# 2020.net
KiCad netlist of a schematic drawn in Altium Designer
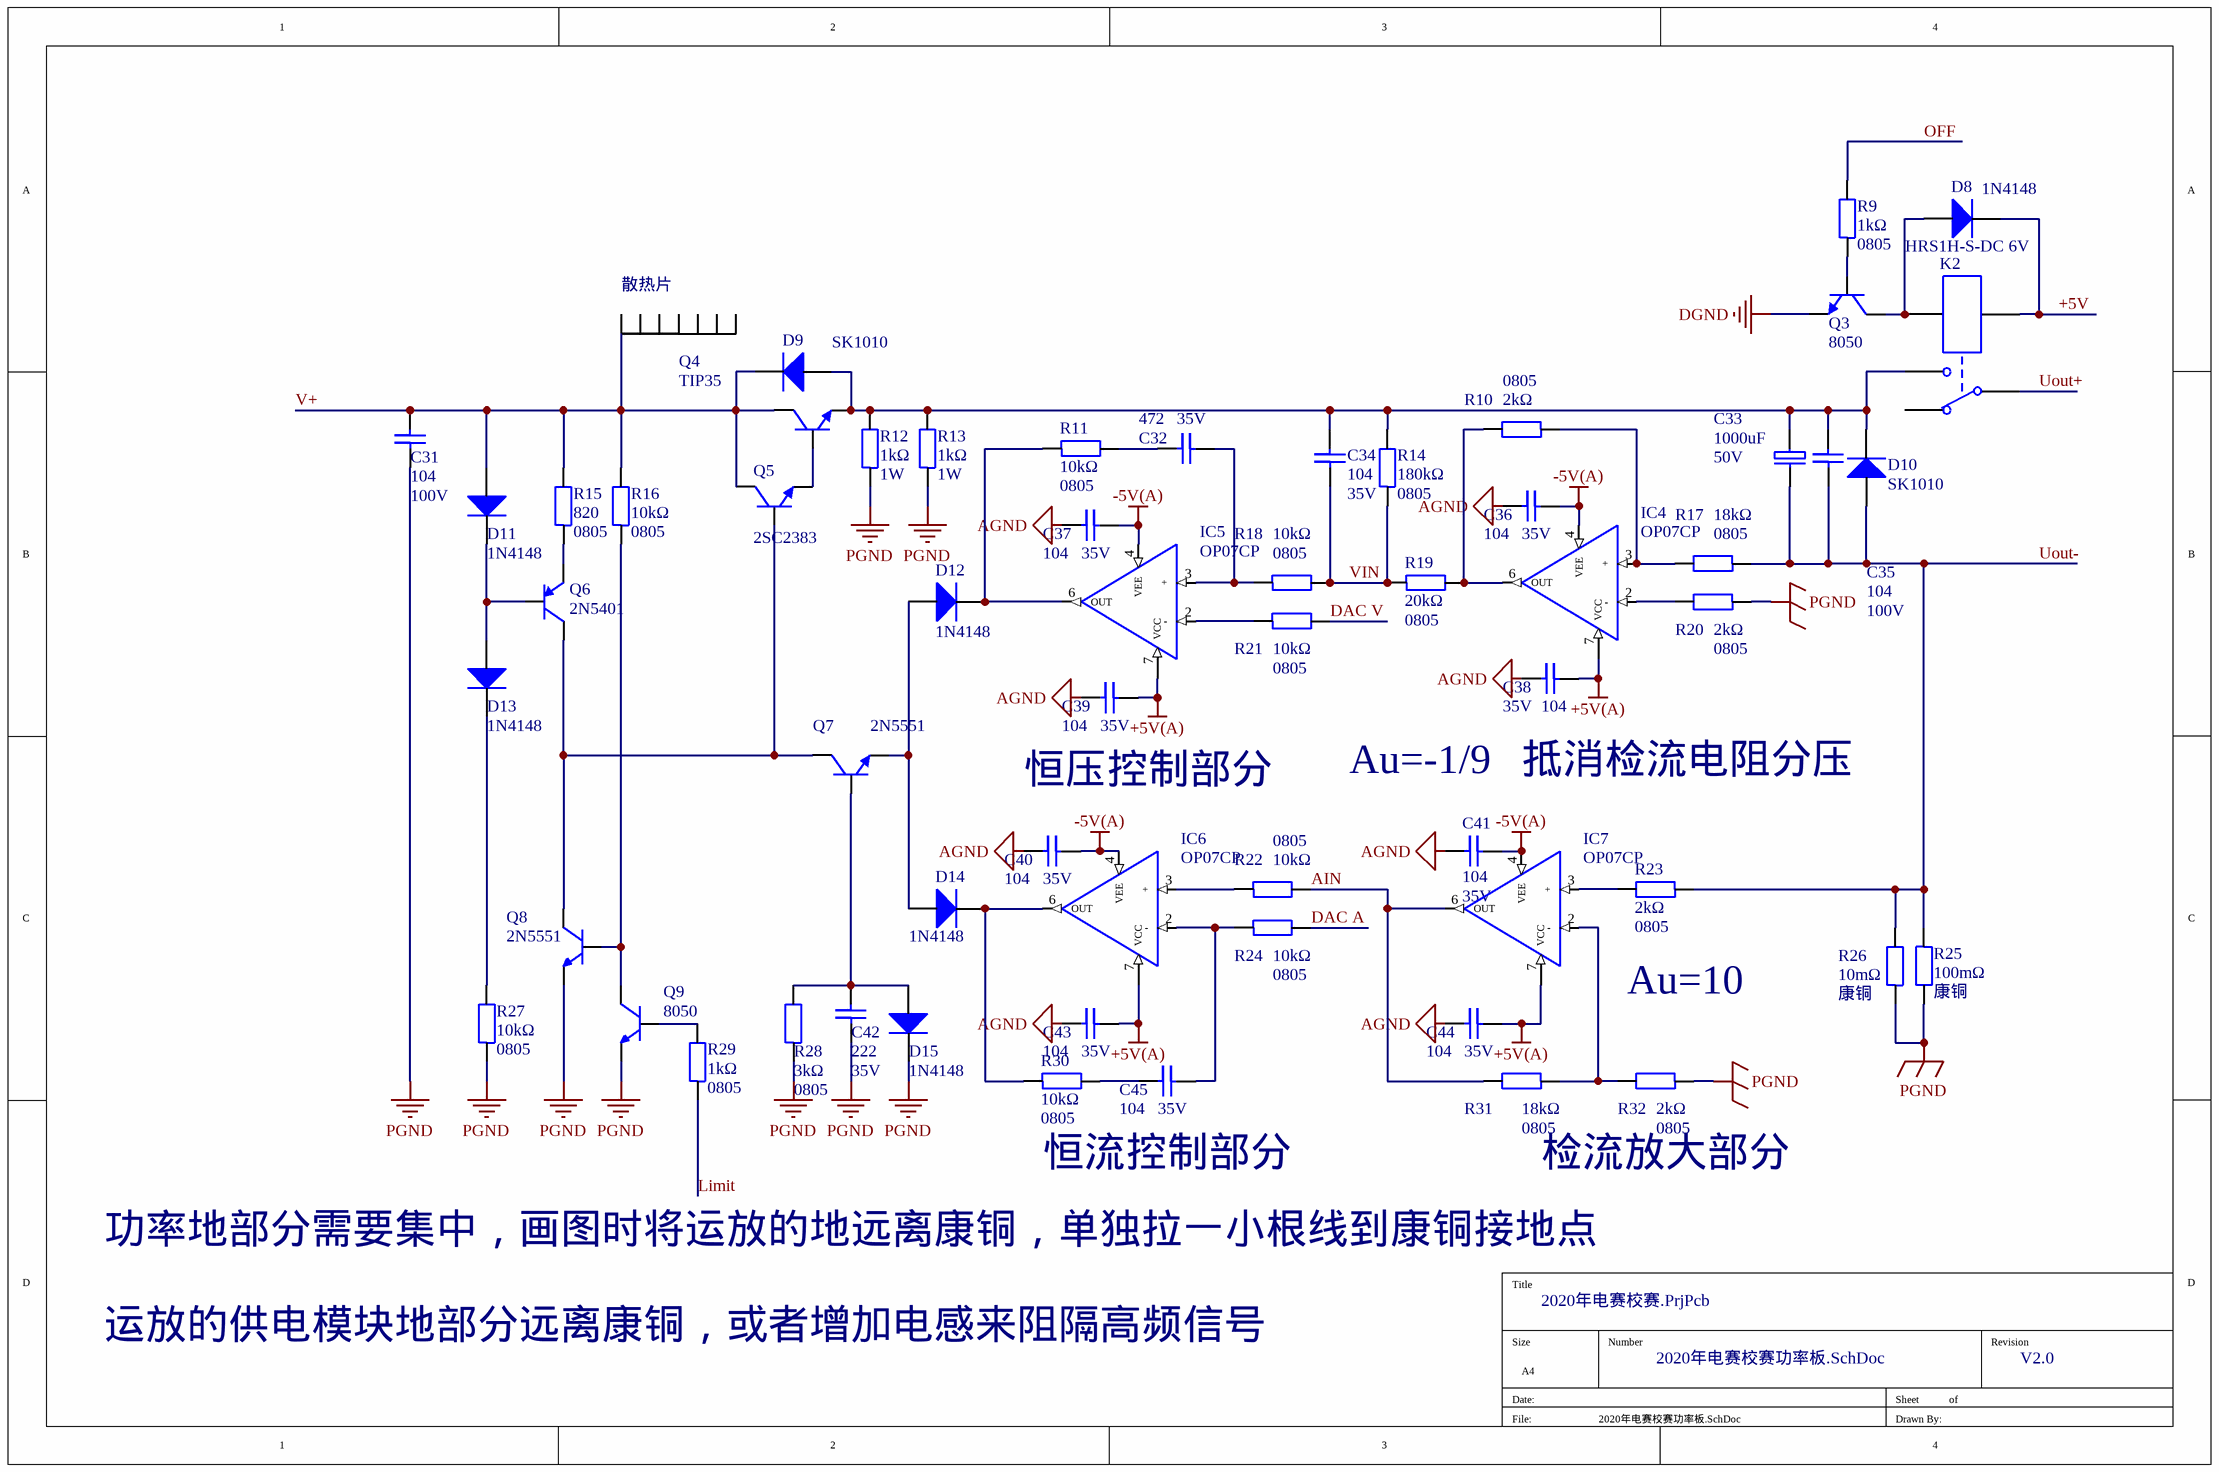
[diagram p0: 2020年电赛校赛功率板.SchDoc]

(export (version "E")
  (design (tool "Eeschema 10.0.6"))
  (components
    (comp (ref "C31")
      (value "104")
      (footprint "C0805")
      (description "无极性电容")
      (fields (field (name "ALTIUM_VALUE") "100V"))
      (libsource (lib "原理图库") (part "104"))
    )
    (comp (ref "C32")
      (value "472")
      (footprint "C0805")
      (description "无极性电容")
      (fields (field (name "ALTIUM_VALUE") "35V"))
      (libsource (lib "原理图库") (part "104"))
    )
    (comp (ref "C33")
      (value "1000uF")
      (footprint "50V 1000uF")
      (description "有极性电容")
      (fields (field (name "ALTIUM_VALUE") "50V"))
      (libsource (lib "原理图库") (part "100uF"))
    )
    (comp (ref "C34")
      (value "104")
      (footprint "C0805")
      (description "无极性电容")
      (fields (field (name "ALTIUM_VALUE") "35V"))
      (libsource (lib "原理图库") (part "104"))
    )
    (comp (ref "C35")
      (value "104")
      (footprint "C0805")
      (description "无极性电容")
      (fields (field (name "ALTIUM_VALUE") "100V"))
      (libsource (lib "原理图库") (part "104"))
    )
    (comp (ref "C36")
      (value "104")
      (footprint "C0805")
      (description "无极性电容")
      (fields (field (name "ALTIUM_VALUE") "35V"))
      (libsource (lib "原理图库") (part "104"))
    )
    (comp (ref "C37")
      (value "104")
      (footprint "C0805")
      (description "无极性电容")
      (fields (field (name "ALTIUM_VALUE") "35V"))
      (libsource (lib "原理图库") (part "104"))
    )
    (comp (ref "C38")
      (value "104")
      (footprint "C0805")
      (description "无极性电容")
      (fields (field (name "ALTIUM_VALUE") "35V"))
      (libsource (lib "原理图库") (part "104"))
    )
    (comp (ref "C39")
      (value "104")
      (footprint "C0805")
      (description "无极性电容")
      (fields (field (name "ALTIUM_VALUE") "35V"))
      (libsource (lib "原理图库") (part "104"))
    )
    (comp (ref "C40")
      (value "104")
      (footprint "C0805")
      (description "无极性电容")
      (fields (field (name "ALTIUM_VALUE") "35V"))
      (libsource (lib "原理图库") (part "104"))
    )
    (comp (ref "C41")
      (value "104")
      (footprint "C0805")
      (description "无极性电容")
      (fields (field (name "ALTIUM_VALUE") "35V"))
      (libsource (lib "原理图库") (part "104"))
    )
    (comp (ref "C42")
      (value "222")
      (footprint "C0805")
      (description "无极性电容")
      (fields (field (name "ALTIUM_VALUE") "35V"))
      (libsource (lib "原理图库") (part "104"))
    )
    (comp (ref "C43")
      (value "104")
      (footprint "C0805")
      (description "无极性电容")
      (fields (field (name "ALTIUM_VALUE") "35V"))
      (libsource (lib "原理图库") (part "104"))
    )
    (comp (ref "C44")
      (value "104")
      (footprint "C0805")
      (description "无极性电容")
      (fields (field (name "ALTIUM_VALUE") "35V"))
      (libsource (lib "原理图库") (part "104"))
    )
    (comp (ref "C45")
      (value "104")
      (footprint "C0805")
      (description "无极性电容")
      (fields (field (name "ALTIUM_VALUE") "35V"))
      (libsource (lib "原理图库") (part "104"))
    )
    (comp (ref "D8")
      (value "1N4148")
      (footprint "LL34")
      (description "二极管")
      (libsource (lib "原理图库") (part "Diode"))
    )
    (comp (ref "D9")
      (value "SK1010")
      (footprint "SMC(DO-214AB)")
      (description "二极管")
      (libsource (lib "原理图库") (part "Diode"))
    )
    (comp (ref "D10")
      (value "SK1010")
      (footprint "SMC(DO-214AB)")
      (description "二极管")
      (libsource (lib "原理图库") (part "Diode"))
    )
    (comp (ref "D11")
      (value "1N4148")
      (footprint "LL34")
      (description "二极管")
      (libsource (lib "原理图库") (part "Diode"))
    )
    (comp (ref "D12")
      (value "1N4148")
      (footprint "LL34")
      (description "二极管")
      (libsource (lib "原理图库") (part "Diode"))
    )
    (comp (ref "D13")
      (value "1N4148")
      (footprint "LL34")
      (description "二极管")
      (libsource (lib "原理图库") (part "Diode"))
    )
    (comp (ref "D14")
      (value "1N4148")
      (footprint "LL34")
      (description "二极管")
      (libsource (lib "原理图库") (part "Diode"))
    )
    (comp (ref "D15")
      (value "1N4148")
      (footprint "LL34")
      (description "二极管")
      (libsource (lib "原理图库") (part "Diode"))
    )
    (comp (ref "IC4")
      (value "OP07CP")
      (footprint "SOP-8(体宽3.8mm)")
      (description "运放")
      (libsource (lib "原理图库") (part "OP07CP"))
    )
    (comp (ref "IC5")
      (value "OP07CP")
      (footprint "SOP-8(体宽3.8mm)")
      (description "运放")
      (libsource (lib "原理图库") (part "OP07CP"))
    )
    (comp (ref "IC6")
      (value "OP07CP")
      (footprint "SOP-8(体宽3.8mm)")
      (description "运放")
      (libsource (lib "原理图库") (part "OP07CP"))
    )
    (comp (ref "IC7")
      (value "OP07CP")
      (footprint "SOP-8(体宽3.8mm)")
      (description "运放")
      (libsource (lib "原理图库") (part "OP07CP"))
    )
    (comp (ref "K2")
      (value "HRS1H-S-DC 6V")
      (footprint "HRS1H-S-DC 6V")
      (description "继电器")
      (libsource (lib "原理图库") (part "HRS1H-S-DC 6V"))
    )
    (comp (ref "Q3")
      (value "8050")
      (footprint "SOT-23")
      (description "三极管")
      (libsource (lib "") (part "NPN_2"))
    )
    (comp (ref "Q4")
      (value "TIP35")
      (footprint "TO-247")
      (description "三极管")
      (libsource (lib "原理图库") (part "NPN"))
    )
    (comp (ref "Q5")
      (value "2SC2383")
      (footprint "TO-92")
      (description "三极管")
      (libsource (lib "") (part "NPN_1"))
    )
    (comp (ref "Q6") (value "2N5401") (footprint "SOT-23") (libsource (lib "原理图库") (part "PNP")))
    (comp (ref "Q7")
      (value "2N5551")
      (footprint "SOT-23")
      (description "三极管")
      (libsource (lib "") (part "NPN_2"))
    )
    (comp (ref "Q8") (value "2N5551") (footprint "SOT-23") (libsource (lib "原理图库") (part "NPN!")))
    (comp (ref "Q9")
      (value "8050")
      (footprint "SOT-23")
      (description "三极管")
      (libsource (lib "原理图库") (part "NPN!"))
    )
    (comp (ref "R9")
      (value "1kΩ")
      (footprint "R0805")
      (description "贴片/直插电阻")
      (fields (field (name "ALTIUM_VALUE") "0805"))
      (libsource (lib "原理图库") (part "10kΩ"))
    )
    (comp (ref "R10")
      (value "2kΩ")
      (footprint "R0805")
      (description "贴片/直插电阻")
      (fields (field (name "ALTIUM_VALUE") "0805"))
      (libsource (lib "原理图库") (part "10kΩ"))
    )
    (comp (ref "R11")
      (value "10kΩ")
      (footprint "R0805")
      (description "贴片/直插电阻")
      (fields (field (name "ALTIUM_VALUE") "0805"))
      (libsource (lib "原理图库") (part "10kΩ"))
    )
    (comp (ref "R12")
      (value "1kΩ")
      (footprint "Res-1W")
      (description "贴片/直插电阻")
      (fields (field (name "ALTIUM_VALUE") "1W"))
      (libsource (lib "原理图库") (part "10kΩ"))
    )
    (comp (ref "R13")
      (value "1kΩ")
      (footprint "Res-1W")
      (description "贴片/直插电阻")
      (fields (field (name "ALTIUM_VALUE") "1W"))
      (libsource (lib "原理图库") (part "10kΩ"))
    )
    (comp (ref "R14")
      (value "180kΩ")
      (footprint "R0805")
      (description "贴片/直插电阻")
      (fields (field (name "ALTIUM_VALUE") "0805"))
      (libsource (lib "原理图库") (part "10kΩ"))
    )
    (comp (ref "R15")
      (value "820")
      (footprint "R0805")
      (description "贴片/直插电阻")
      (fields (field (name "ALTIUM_VALUE") "0805"))
      (libsource (lib "原理图库") (part "10kΩ"))
    )
    (comp (ref "R16")
      (value "10kΩ")
      (footprint "R0805")
      (description "贴片/直插电阻")
      (fields (field (name "ALTIUM_VALUE") "0805"))
      (libsource (lib "原理图库") (part "10kΩ"))
    )
    (comp (ref "R17")
      (value "18kΩ")
      (footprint "R0805")
      (description "贴片/直插电阻")
      (fields (field (name "ALTIUM_VALUE") "0805"))
      (libsource (lib "原理图库") (part "10kΩ"))
    )
    (comp (ref "R18")
      (value "10kΩ")
      (footprint "R0805")
      (description "贴片/直插电阻")
      (fields (field (name "ALTIUM_VALUE") "0805"))
      (libsource (lib "原理图库") (part "10kΩ"))
    )
    (comp (ref "R19")
      (value "20kΩ")
      (footprint "R0805")
      (description "贴片/直插电阻")
      (fields (field (name "ALTIUM_VALUE") "0805"))
      (libsource (lib "原理图库") (part "10kΩ"))
    )
    (comp (ref "R20")
      (value "2kΩ")
      (footprint "R0805")
      (description "贴片/直插电阻")
      (fields (field (name "ALTIUM_VALUE") "0805"))
      (libsource (lib "原理图库") (part "10kΩ"))
    )
    (comp (ref "R21")
      (value "10kΩ")
      (footprint "R0805")
      (description "贴片/直插电阻")
      (fields (field (name "ALTIUM_VALUE") "0805"))
      (libsource (lib "原理图库") (part "10kΩ"))
    )
    (comp (ref "R22")
      (value "10kΩ")
      (footprint "R0805")
      (description "贴片/直插电阻")
      (fields (field (name "ALTIUM_VALUE") "0805"))
      (libsource (lib "原理图库") (part "10kΩ"))
    )
    (comp (ref "R23")
      (value "2kΩ")
      (footprint "R0805")
      (description "贴片/直插电阻")
      (fields (field (name "ALTIUM_VALUE") "0805"))
      (libsource (lib "原理图库") (part "10kΩ"))
    )
    (comp (ref "R24")
      (value "10kΩ")
      (footprint "R0805")
      (description "贴片/直插电阻")
      (fields (field (name "ALTIUM_VALUE") "0805"))
      (libsource (lib "原理图库") (part "10kΩ"))
    )
    (comp (ref "R25")
      (value "100mΩ")
      (footprint "100mΩ康铜")
      (description "贴片/直插电阻")
      (fields (field (name "ALTIUM_VALUE") "康铜"))
      (libsource (lib "原理图库") (part "10kΩ"))
    )
    (comp (ref "R26")
      (value "10mΩ")
      (footprint "10mΩ康铜")
      (description "贴片/直插电阻")
      (fields (field (name "ALTIUM_VALUE") "康铜"))
      (libsource (lib "原理图库") (part "10kΩ"))
    )
    (comp (ref "R27")
      (value "10kΩ")
      (footprint "R0805")
      (description "贴片/直插电阻")
      (fields (field (name "ALTIUM_VALUE") "0805"))
      (libsource (lib "原理图库") (part "10kΩ"))
    )
    (comp (ref "R28")
      (value "3kΩ")
      (footprint "R0805")
      (description "贴片/直插电阻")
      (fields (field (name "ALTIUM_VALUE") "0805"))
      (libsource (lib "原理图库") (part "10kΩ"))
    )
    (comp (ref "R29")
      (value "1kΩ")
      (footprint "R0805")
      (description "贴片/直插电阻")
      (fields (field (name "ALTIUM_VALUE") "0805"))
      (libsource (lib "原理图库") (part "10kΩ"))
    )
    (comp (ref "R30")
      (value "10kΩ")
      (footprint "R0805")
      (description "贴片/直插电阻")
      (fields (field (name "ALTIUM_VALUE") "0805"))
      (libsource (lib "原理图库") (part "10kΩ"))
    )
    (comp (ref "R31")
      (value "18kΩ")
      (footprint "R0805")
      (description "贴片/直插电阻")
      (fields (field (name "ALTIUM_VALUE") "0805"))
      (libsource (lib "原理图库") (part "10kΩ"))
    )
    (comp (ref "R32")
      (value "2kΩ")
      (footprint "R0805")
      (description "贴片/直插电阻")
      (fields (field (name "ALTIUM_VALUE") "0805"))
      (libsource (lib "原理图库") (part "10kΩ"))
    )
    (comp (ref "S1") (value "散热片") (footprint "散热片") (libsource (lib "原理图库") (part "散热片")))
  )
  (nets
    (net (code "1") (name "+5V(A)") (class "Default")
      (node (ref "C38") (pin "2") (pintype "passive"))
      (node (ref "C39") (pin "2") (pintype "passive"))
      (node (ref "C43") (pin "2") (pintype "passive"))
      (node (ref "C44") (pin "2") (pintype "passive"))
      (node (ref "IC4") (pin "7") (pinfunction "VCC_7") (pintype "input"))
      (node (ref "IC5") (pin "7") (pinfunction "VCC_7") (pintype "input"))
      (node (ref "IC6") (pin "7") (pinfunction "VCC_7") (pintype "input"))
      (node (ref "IC7") (pin "7") (pinfunction "VCC_7") (pintype "input"))
    )
    (net (code "2") (name "-5V(A)") (class "Default")
      (node (ref "C36") (pin "2") (pintype "passive"))
      (node (ref "C37") (pin "2") (pintype "passive"))
      (node (ref "C40") (pin "2") (pintype "passive"))
      (node (ref "C41") (pin "2") (pintype "passive"))
      (node (ref "IC4") (pin "4") (pinfunction "VEE_4") (pintype "input"))
      (node (ref "IC5") (pin "4") (pinfunction "VEE_4") (pintype "input"))
      (node (ref "IC6") (pin "4") (pinfunction "VEE_4") (pintype "input"))
      (node (ref "IC7") (pin "4") (pinfunction "VEE_4") (pintype "input"))
    )
    (net (code "3") (name "/+5V") (class "Default")
      (node (ref "D8") (pin "2") (pinfunction "K_2") (pintype "passive"))
      (node (ref "K2") (pin "2") (pinfunction "2_2") (pintype "passive"))
    )
    (net (code "4") (name "/AIN") (class "Default")
      (node (ref "IC7") (pin "6") (pinfunction "OUT_6") (pintype "output"))
      (node (ref "R22") (pin "2") (pintype "passive"))
      (node (ref "R31") (pin "2") (pintype "passive"))
    )
    (net (code "5") (name "/DAC A") (class "Default") (node (ref "R24") (pin "2") (pintype "passive")))
    (net (code "6") (name "/DAC V") (class "Default") (node (ref "R21") (pin "2") (pintype "passive")))
    (net (code "7") (name "/Limit") (class "Default") (node (ref "R29") (pin "1") (pintype "passive")))
    (net (code "8") (name "/OFF") (class "Default") (node (ref "R9") (pin "2") (pintype "passive")))
    (net (code "9") (name "/Uout+") (class "Default")
      (node (ref "K2") (pin "4") (pinfunction "4_4") (pintype "passive"))
    )
    (net (code "10") (name "/Uout-") (class "Default")
      (node (ref "C33") (pin "2") (pinfunction "-_2") (pintype "passive"))
      (node (ref "C35") (pin "1") (pintype "passive"))
      (node (ref "D10") (pin "1") (pinfunction "A_1") (pintype "passive"))
      (node (ref "R17") (pin "1") (pintype "passive"))
      (node (ref "R23") (pin "1") (pintype "passive"))
      (node (ref "R25") (pin "1") (pintype "passive"))
      (node (ref "R26") (pin "2") (pintype "passive"))
    )
    (net (code "11") (name "/V+") (class "Default")
      (node (ref "C31") (pin "2") (pintype "passive"))
      (node (ref "D11") (pin "1") (pinfunction "A_1") (pintype "passive"))
      (node (ref "D9") (pin "2") (pinfunction "K_2") (pintype "passive"))
      (node (ref "Q4") (pin "2") (pinfunction "C_2") (pintype "passive"))
      (node (ref "Q5") (pin "2") (pinfunction "C_2") (pintype "passive"))
      (node (ref "R15") (pin "2") (pintype "passive"))
      (node (ref "R16") (pin "2") (pintype "passive"))
      (node (ref "S1") (pin "1") (pintype "passive"))
    )
    (net (code "12") (name "/VIN") (class "Default")
      (node (ref "C34") (pin "1") (pintype "passive"))
      (node (ref "R14") (pin "1") (pintype "passive"))
      (node (ref "R18") (pin "2") (pintype "passive"))
      (node (ref "R19") (pin "1") (pintype "passive"))
    )
    (net (code "13") (name "AGND") (class "Default")
      (node (ref "C36") (pin "1") (pintype "passive"))
      (node (ref "C37") (pin "1") (pintype "passive"))
      (node (ref "C38") (pin "1") (pintype "passive"))
      (node (ref "C39") (pin "1") (pintype "passive"))
      (node (ref "C40") (pin "1") (pintype "passive"))
      (node (ref "C41") (pin "1") (pintype "passive"))
      (node (ref "C43") (pin "1") (pintype "passive"))
      (node (ref "C44") (pin "1") (pintype "passive"))
    )
    (net (code "14") (name "DGND") (class "Default")
      (node (ref "Q3") (pin "2") (pinfunction "E_2") (pintype "passive"))
    )
    (net (code "15") (name "Net-(C32-Pad1)") (class "Default")
      (node (ref "C32") (pin "1") (pintype "passive"))
      (node (ref "R11") (pin "2") (pintype "passive"))
    )
    (net (code "16") (name "Net-(C33-+)") (class "Default")
      (node (ref "C33") (pin "1") (pinfunction "+_1") (pintype "passive"))
      (node (ref "C34") (pin "2") (pintype "passive"))
      (node (ref "C35") (pin "2") (pintype "passive"))
      (node (ref "D10") (pin "2") (pinfunction "K_2") (pintype "passive"))
      (node (ref "D9") (pin "1") (pinfunction "A_1") (pintype "passive"))
      (node (ref "K2") (pin "6") (pinfunction "6_6") (pintype "passive"))
      (node (ref "Q4") (pin "3") (pinfunction "E_3") (pintype "passive"))
      (node (ref "R12") (pin "2") (pintype "passive"))
      (node (ref "R13") (pin "2") (pintype "passive"))
      (node (ref "R14") (pin "2") (pintype "passive"))
    )
    (net (code "17") (name "Net-(C45-Pad1)") (class "Default")
      (node (ref "C45") (pin "1") (pintype "passive"))
      (node (ref "R30") (pin "2") (pintype "passive"))
    )
    (net (code "18") (name "Net-(D8-A)") (class "Default")
      (node (ref "D8") (pin "1") (pinfunction "A_1") (pintype "passive"))
      (node (ref "K2") (pin "5") (pinfunction "5_5") (pintype "passive"))
      (node (ref "Q3") (pin "3") (pinfunction "C_3") (pintype "passive"))
    )
    (net (code "19") (name "Net-(D11-K)") (class "Default")
      (node (ref "D11") (pin "2") (pinfunction "K_2") (pintype "passive"))
      (node (ref "D13") (pin "1") (pinfunction "A_1") (pintype "passive"))
      (node (ref "Q6") (pin "1") (pinfunction "B_1") (pintype "passive"))
    )
    (net (code "20") (name "Net-(D12-A)") (class "Default")
      (node (ref "D12") (pin "1") (pinfunction "A_1") (pintype "passive"))
      (node (ref "D14") (pin "1") (pinfunction "A_1") (pintype "passive"))
      (node (ref "Q7") (pin "2") (pinfunction "E_2") (pintype "passive"))
    )
    (net (code "21") (name "Net-(D12-K)") (class "Default")
      (node (ref "D12") (pin "2") (pinfunction "K_2") (pintype "passive"))
      (node (ref "IC5") (pin "6") (pinfunction "OUT_6") (pintype "output"))
      (node (ref "R11") (pin "1") (pintype "passive"))
    )
    (net (code "22") (name "Net-(D13-K)") (class "Default")
      (node (ref "D13") (pin "2") (pinfunction "K_2") (pintype "passive"))
      (node (ref "R27") (pin "2") (pintype "passive"))
    )
    (net (code "23") (name "Net-(D14-K)") (class "Default")
      (node (ref "D14") (pin "2") (pinfunction "K_2") (pintype "passive"))
      (node (ref "IC6") (pin "6") (pinfunction "OUT_6") (pintype "output"))
      (node (ref "R30") (pin "1") (pintype "passive"))
    )
    (net (code "24") (name "Net-(D15-A)") (class "Default")
      (node (ref "C42") (pin "2") (pintype "passive"))
      (node (ref "D15") (pin "1") (pinfunction "A_1") (pintype "passive"))
      (node (ref "Q7") (pin "1") (pinfunction "B_1") (pintype "passive"))
      (node (ref "R28") (pin "2") (pintype "passive"))
    )
    (net (code "25") (name "Net-(IC4-+)") (class "Default")
      (node (ref "IC4") (pin "3") (pinfunction "+_3") (pintype "input"))
      (node (ref "R10") (pin "1") (pintype "passive"))
      (node (ref "R17") (pin "2") (pintype "passive"))
    )
    (net (code "26") (name "Net-(IC4--)") (class "Default")
      (node (ref "IC4") (pin "2") (pinfunction "-_2") (pintype "input"))
      (node (ref "R20") (pin "2") (pintype "passive"))
    )
    (net (code "27") (name "Net-(IC4-OUT)") (class "Default")
      (node (ref "IC4") (pin "6") (pinfunction "OUT_6") (pintype "output"))
      (node (ref "R10") (pin "2") (pintype "passive"))
      (node (ref "R19") (pin "2") (pintype "passive"))
    )
    (net (code "28") (name "Net-(IC5-+)") (class "Default")
      (node (ref "C32") (pin "2") (pintype "passive"))
      (node (ref "IC5") (pin "3") (pinfunction "+_3") (pintype "input"))
      (node (ref "R18") (pin "1") (pintype "passive"))
    )
    (net (code "29") (name "Net-(IC5--)") (class "Default")
      (node (ref "IC5") (pin "2") (pinfunction "-_2") (pintype "input"))
      (node (ref "R21") (pin "1") (pintype "passive"))
    )
    (net (code "30") (name "Net-(IC6-+)") (class "Default")
      (node (ref "IC6") (pin "3") (pinfunction "+_3") (pintype "input"))
      (node (ref "R22") (pin "1") (pintype "passive"))
    )
    (net (code "31") (name "Net-(IC6--)") (class "Default")
      (node (ref "C45") (pin "2") (pintype "passive"))
      (node (ref "IC6") (pin "2") (pinfunction "-_2") (pintype "input"))
      (node (ref "R24") (pin "1") (pintype "passive"))
    )
    (net (code "32") (name "Net-(IC7-+)") (class "Default")
      (node (ref "IC7") (pin "3") (pinfunction "+_3") (pintype "input"))
      (node (ref "R23") (pin "2") (pintype "passive"))
    )
    (net (code "33") (name "Net-(IC7--)") (class "Default")
      (node (ref "IC7") (pin "2") (pinfunction "-_2") (pintype "input"))
      (node (ref "R31") (pin "1") (pintype "passive"))
      (node (ref "R32") (pin "2") (pintype "passive"))
    )
    (net (code "34") (name "Net-(Q3-B)") (class "Default")
      (node (ref "Q3") (pin "1") (pinfunction "B_1") (pintype "passive"))
      (node (ref "R9") (pin "1") (pintype "passive"))
    )
    (net (code "35") (name "Net-(Q4-B)") (class "Default")
      (node (ref "Q4") (pin "1") (pinfunction "B_1") (pintype "passive"))
      (node (ref "Q5") (pin "1") (pinfunction "E_1") (pintype "passive"))
    )
    (net (code "36") (name "Net-(Q5-B)") (class "Default")
      (node (ref "Q5") (pin "3") (pinfunction "B_3") (pintype "passive"))
      (node (ref "Q6") (pin "3") (pinfunction "C_3") (pintype "passive"))
      (node (ref "Q7") (pin "3") (pinfunction "C_3") (pintype "passive"))
      (node (ref "Q8") (pin "3") (pinfunction "C_3") (pintype "passive"))
    )
    (net (code "37") (name "Net-(Q6-E)") (class "Default")
      (node (ref "Q6") (pin "2") (pinfunction "E_2") (pintype "passive"))
      (node (ref "R15") (pin "1") (pintype "passive"))
    )
    (net (code "38") (name "Net-(Q8-B)") (class "Default")
      (node (ref "Q8") (pin "1") (pinfunction "B_1") (pintype "passive"))
      (node (ref "Q9") (pin "3") (pinfunction "C_3") (pintype "passive"))
      (node (ref "R16") (pin "1") (pintype "passive"))
    )
    (net (code "39") (name "Net-(Q9-B)") (class "Default")
      (node (ref "Q9") (pin "1") (pinfunction "B_1") (pintype "passive"))
      (node (ref "R29") (pin "2") (pintype "passive"))
    )
    (net (code "40") (name "PGND") (class "Default")
      (node (ref "C31") (pin "1") (pintype "passive"))
      (node (ref "C42") (pin "1") (pintype "passive"))
      (node (ref "D15") (pin "2") (pinfunction "K_2") (pintype "passive"))
      (node (ref "Q8") (pin "2") (pinfunction "E_2") (pintype "passive"))
      (node (ref "Q9") (pin "2") (pinfunction "E_2") (pintype "passive"))
      (node (ref "R12") (pin "1") (pintype "passive"))
      (node (ref "R13") (pin "1") (pintype "passive"))
      (node (ref "R20") (pin "1") (pintype "passive"))
      (node (ref "R25") (pin "2") (pintype "passive"))
      (node (ref "R26") (pin "1") (pintype "passive"))
      (node (ref "R27") (pin "1") (pintype "passive"))
      (node (ref "R28") (pin "1") (pintype "passive"))
      (node (ref "R32") (pin "1") (pintype "passive"))
    )
    (net (code "41") (name "unconnected-(K2-Pad1)") (class "Default")
      (node (ref "K2") (pin "1") (pinfunction "1_1") (pintype "passive"))
    )
    (net (code "42") (name "unconnected-(S1-Pad2)") (class "Default")
      (node (ref "S1") (pin "2") (pintype "passive"))
    )
  )
)
